# BLT_Preliminary_Avionics_Schematic_Brand.net
KiCad netlist of a schematic drawn in EAGLE
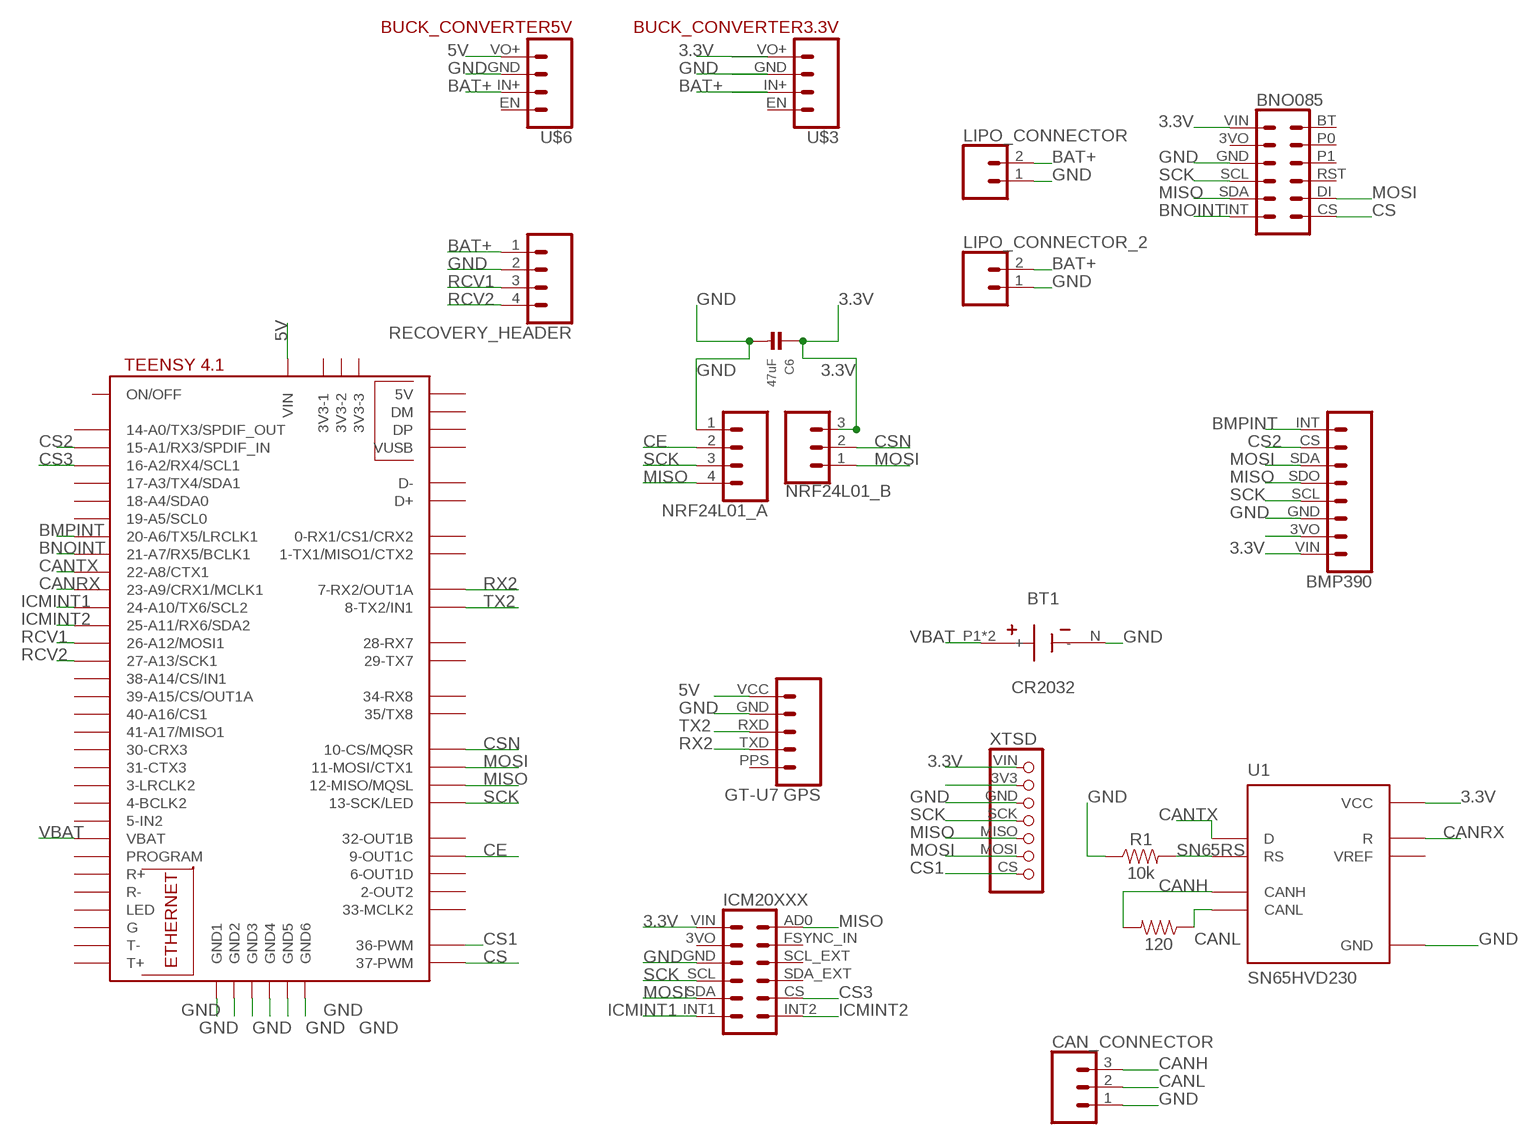
[diagram p0: schematic, sheet 1]

(export (version "E")
  (design (tool "Eeschema 10.0.6"))
  (components
    (comp (ref "120")
      (value "RESISTOR1206")
      (footprint "eagle-import:1206")
      (libsource (lib "eagle-import") (part "RESISTOR1206"))
    )
    (comp (ref "BT1")
      (value "CR2032")
      (footprint "eagle-import:BAT_3003")
      (fields (field (name "MANUFACTURER") "Keystone Electronics") (field (name "MPN") "3003"))
      (libsource (lib "eagle-import") (part "COIN-CELL-THM-3P?--3003CR2032"))
    )
    (comp (ref "C6")
      (value "47uF")
      (footprint "eagle-import:0805")
      (libsource (lib "eagle-import") (part "CAP_CERAMIC0805"))
    )
    (comp (ref "CAN_CONNECTOR")
      (value "CONN_03")
      (footprint "eagle-import:1X03")
      (libsource (lib "eagle-import") (part "CONN_03"))
    )
    (comp (ref "LIPO_CONNECTOR")
      (value "CONN_02PTH4")
      (footprint "eagle-import:1X02_XTRA_BIG")
      (libsource (lib "eagle-import") (part "CONN_02PTH4"))
    )
    (comp (ref "LIPO_CONNECTOR_2")
      (value "CONN_02")
      (footprint "eagle-import:1X02")
      (libsource (lib "eagle-import") (part "CONN_02"))
    )
    (comp (ref "NRF24L01_A")
      (value "CONN_04")
      (footprint "eagle-import:1X04")
      (libsource (lib "eagle-import") (part "CONN_04"))
    )
    (comp (ref "NRF24L01_B")
      (value "CONN_03")
      (footprint "eagle-import:1X03")
      (libsource (lib "eagle-import") (part "CONN_03"))
    )
    (comp (ref "R1")
      (value "10k")
      (footprint "eagle-import:0603")
      (libsource (lib "eagle-import") (part "10KOHM-0603-1/10W-1%"))
    )
    (comp (ref "RECOVERY_HEADER")
      (value "CONN_04")
      (footprint "eagle-import:1X04")
      (libsource (lib "eagle-import") (part "CONN_04"))
    )
    (comp (ref "U$1")
      (value "TEENSY41")
      (footprint "eagle-import:TEENSY41")
      (libsource (lib "eagle-import") (part "TEENSY41"))
    )
    (comp (ref "U$2")
      (value "BMP390")
      (footprint "eagle-import:MICROBUILDER_1X08_ROUND")
      (libsource (lib "eagle-import") (part "BMP390"))
    )
    (comp (ref "U$3")
      (value "BUCK_CONVERTER3.3V")
      (footprint "eagle-import:1X04")
      (fields (field (name "VOLTAGE") "3.3V"))
      (libsource (lib "eagle-import") (part "BUCK_CONVERTER3.3V"))
    )
    (comp (ref "U$4")
      (value "GT-U7_GPS")
      (footprint "eagle-import:1X05")
      (libsource (lib "eagle-import") (part "GT-U7_GPS"))
    )
    (comp (ref "U$5")
      (value "XTSDXTSD_PINS")
      (footprint "eagle-import:1X07")
      (libsource (lib "eagle-import") (part "XTSDXTSD_PINS"))
    )
    (comp (ref "U$6")
      (value "BUCK_CONVERTER5V")
      (footprint "eagle-import:1X04")
      (fields (field (name "VOLTAGE") "5V"))
      (libsource (lib "eagle-import") (part "BUCK_CONVERTER5V"))
    )
    (comp (ref "U$7")
      (value "BNO085")
      (footprint "eagle-import:MICROBUILDER_1X06_ROUND_70")
      (libsource (lib "eagle-import") (part "BNO085"))
    )
    (comp (ref "U$8")
      (value "ICM20XXX")
      (footprint "eagle-import:1X06")
      (libsource (lib "eagle-import") (part "ICM20XXX"))
    )
    (comp (ref "U1")
      (value "SN65HVD230")
      (footprint "eagle-import:SOIC127P599X175-8N")
      (fields (field (name "MF") "Texas Instruments"))
      (libsource (lib "eagle-import") (part "SN65HVD230"))
    )
  )
  (nets
    (net (code "1") (name "/3.3V") (class "Default")
      (node (ref "C6") (pin "1") (pinfunction "P$1_1") (pintype "passive"))
      (node (ref "NRF24L01_B") (pin "3") (pinfunction "3_3") (pintype "passive"))
      (node (ref "U$2") (pin "VIN") (pinfunction "VIN_VIN") (pintype "passive"))
      (node (ref "U$3") (pin "VO+") (pinfunction "VO+_VO+") (pintype "passive"))
      (node (ref "U$5") (pin "VIN") (pinfunction "VIN_VIN") (pintype "passive"))
      (node (ref "U$7") (pin "VIN") (pinfunction "VIN_VIN") (pintype "passive"))
      (node (ref "U$8") (pin "VIN") (pinfunction "VCC_VIN") (pintype "passive"))
      (node (ref "U1") (pin "3") (pinfunction "VCC_3") (pintype "power_in"))
    )
    (net (code "2") (name "/5V") (class "Default")
      (node (ref "U$1") (pin "VIN") (pinfunction "VIN_VIN") (pintype "bidirectional"))
      (node (ref "U$4") (pin "VCC") (pinfunction "VCC_VCC") (pintype "passive"))
      (node (ref "U$6") (pin "VO+") (pinfunction "VO+_VO+") (pintype "passive"))
    )
    (net (code "3") (name "/BAT+") (class "Default")
      (node (ref "LIPO_CONNECTOR") (pin "2") (pinfunction "2_2") (pintype "passive"))
      (node (ref "LIPO_CONNECTOR_2") (pin "2") (pinfunction "2_2") (pintype "passive"))
      (node (ref "RECOVERY_HEADER") (pin "1") (pinfunction "1_1") (pintype "passive"))
      (node (ref "U$3") (pin "IN+") (pinfunction "IN+_IN+") (pintype "passive"))
      (node (ref "U$6") (pin "IN+") (pinfunction "IN+_IN+") (pintype "passive"))
    )
    (net (code "4") (name "/BMPINT") (class "Default")
      (node (ref "U$1") (pin "20-A6/TX5/LRCLK1") (pinfunction "20-A6/TX5/LRCLK1_20-A6/TX5/LRCLK1") (pintype "bidirectional"))
      (node (ref "U$2") (pin "INT") (pinfunction "INT_INT") (pintype "passive"))
    )
    (net (code "5") (name "/BNOINT") (class "Default")
      (node (ref "U$1") (pin "21-A7/RX5/BCLK1") (pinfunction "21-A7/RX5/BCLK1_21-A7/RX5/BCLK1") (pintype "bidirectional"))
      (node (ref "U$7") (pin "INT") (pinfunction "INT_INT") (pintype "passive"))
    )
    (net (code "6") (name "/CANH") (class "Default")
      (node (ref "120") (pin "2") (pinfunction "2_2") (pintype "passive"))
      (node (ref "CAN_CONNECTOR") (pin "3") (pinfunction "3_3") (pintype "passive"))
      (node (ref "U1") (pin "7") (pinfunction "CANH_7") (pintype "bidirectional"))
    )
    (net (code "7") (name "/CANL") (class "Default")
      (node (ref "120") (pin "1") (pinfunction "1_1") (pintype "passive"))
      (node (ref "CAN_CONNECTOR") (pin "2") (pinfunction "2_2") (pintype "passive"))
      (node (ref "U1") (pin "6") (pinfunction "CANL_6") (pintype "bidirectional"))
    )
    (net (code "8") (name "/CANRX") (class "Default")
      (node (ref "U$1") (pin "23-A9/CRX1/MCLK1") (pinfunction "23-A9/CRX1/MCLK1_23-A9/CRX1/MCLK1") (pintype "bidirectional"))
      (node (ref "U1") (pin "4") (pinfunction "R_4") (pintype "output"))
    )
    (net (code "9") (name "/CANTX") (class "Default")
      (node (ref "U$1") (pin "22-A8/CTX1") (pinfunction "22-A8/CTX1_22-A8/CTX1") (pintype "bidirectional"))
      (node (ref "U1") (pin "1") (pinfunction "D_1") (pintype "input"))
    )
    (net (code "10") (name "/CE") (class "Default")
      (node (ref "NRF24L01_A") (pin "2") (pinfunction "2_2") (pintype "passive"))
      (node (ref "U$1") (pin "9-OUT1C") (pinfunction "9-OUT1C_9-OUT1C") (pintype "bidirectional"))
    )
    (net (code "11") (name "/CS") (class "Default")
      (node (ref "U$1") (pin "37-PWM") (pinfunction "37-PWM_37-PWM") (pintype "bidirectional"))
      (node (ref "U$7") (pin "CS") (pinfunction "CS_CS") (pintype "passive"))
    )
    (net (code "12") (name "/CS1") (class "Default")
      (node (ref "U$1") (pin "36-PWM") (pinfunction "36-PWM_36-PWM") (pintype "bidirectional"))
      (node (ref "U$5") (pin "CS") (pinfunction "CS_CS") (pintype "passive"))
    )
    (net (code "13") (name "/CS2") (class "Default")
      (node (ref "U$1") (pin "15-A1/RX3/SPDIF_IN") (pinfunction "15-A1/RX3/SPDIF_IN_15-A1/RX3/SPDIF_IN") (pintype "bidirectional"))
      (node (ref "U$2") (pin "CS") (pinfunction "CS_CS") (pintype "passive"))
    )
    (net (code "14") (name "/CS3") (class "Default")
      (node (ref "U$1") (pin "16-A2/RX4/SCL1") (pinfunction "16-A2/RX4/SCL1_16-A2/RX4/SCL1") (pintype "bidirectional"))
      (node (ref "U$8") (pin "CS") (pinfunction "CS_CS") (pintype "passive"))
    )
    (net (code "15") (name "/CSN") (class "Default")
      (node (ref "NRF24L01_B") (pin "2") (pinfunction "2_2") (pintype "passive"))
      (node (ref "U$1") (pin "10-CS\\MQSR") (pinfunction "10-CS/MQSR_10-CS\\MQSR") (pintype "bidirectional"))
    )
    (net (code "16") (name "/GND") (class "Default")
      (node (ref "BT1") (pin "N") (pinfunction "-_N") (pintype "bidirectional"))
      (node (ref "C6") (pin "2") (pinfunction "P$2_2") (pintype "passive"))
      (node (ref "CAN_CONNECTOR") (pin "1") (pinfunction "1_1") (pintype "passive"))
      (node (ref "LIPO_CONNECTOR") (pin "1") (pinfunction "1_1") (pintype "passive"))
      (node (ref "LIPO_CONNECTOR_2") (pin "1") (pinfunction "1_1") (pintype "passive"))
      (node (ref "NRF24L01_A") (pin "1") (pinfunction "1_1") (pintype "passive"))
      (node (ref "R1") (pin "1") (pinfunction "1_1") (pintype "passive"))
      (node (ref "RECOVERY_HEADER") (pin "2") (pinfunction "2_2") (pintype "passive"))
      (node (ref "U$1") (pin "GND1") (pinfunction "GND1_GND1") (pintype "bidirectional"))
      (node (ref "U$1") (pin "GND2") (pinfunction "GND2_GND2") (pintype "bidirectional"))
      (node (ref "U$1") (pin "GND3") (pinfunction "GND3_GND3") (pintype "bidirectional"))
      (node (ref "U$1") (pin "GND4") (pinfunction "GND4_GND4") (pintype "bidirectional"))
      (node (ref "U$1") (pin "GND5") (pinfunction "GND5_GND5") (pintype "bidirectional"))
      (node (ref "U$1") (pin "GND6") (pinfunction "GND6_GND6") (pintype "bidirectional"))
      (node (ref "U$2") (pin "GND") (pinfunction "GND_GND") (pintype "passive"))
      (node (ref "U$3") (pin "GND") (pinfunction "GND_GND") (pintype "passive"))
      (node (ref "U$4") (pin "GND") (pinfunction "GND_GND") (pintype "passive"))
      (node (ref "U$5") (pin "GND") (pinfunction "GND_GND") (pintype "passive"))
      (node (ref "U$6") (pin "GND") (pinfunction "GND_GND") (pintype "passive"))
      (node (ref "U$7") (pin "GND") (pinfunction "GND_GND") (pintype "passive"))
      (node (ref "U$8") (pin "GND") (pinfunction "GND_GND") (pintype "passive"))
      (node (ref "U1") (pin "2") (pinfunction "GND_2") (pintype "power_in"))
    )
    (net (code "17") (name "/ICMINT1") (class "Default")
      (node (ref "U$1") (pin "24-A10/TX6/SCL2") (pinfunction "24-A10/TX6/SCL2_24-A10/TX6/SCL2") (pintype "bidirectional"))
      (node (ref "U$8") (pin "INT1") (pinfunction "INT1_INT1") (pintype "passive"))
    )
    (net (code "18") (name "/ICMINT2") (class "Default")
      (node (ref "U$1") (pin "25-A11/RX6/SDA2") (pinfunction "25-A11/RX6/SDA2_25-A11/RX6/SDA2") (pintype "bidirectional"))
      (node (ref "U$8") (pin "INT2") (pinfunction "INT2_INT2") (pintype "passive"))
    )
    (net (code "19") (name "/MISO") (class "Default")
      (node (ref "NRF24L01_A") (pin "4") (pinfunction "4_4") (pintype "passive"))
      (node (ref "U$1") (pin "12-MISO/MQSL") (pinfunction "12-MISO/MQSL_12-MISO/MQSL") (pintype "bidirectional"))
      (node (ref "U$2") (pin "SDO") (pinfunction "SDO_SDO") (pintype "passive"))
      (node (ref "U$5") (pin "MISO") (pinfunction "MISO_MISO") (pintype "passive"))
      (node (ref "U$7") (pin "SDA") (pinfunction "SDA_SDA") (pintype "passive"))
      (node (ref "U$8") (pin "AD0") (pinfunction "AD0_AD0") (pintype "passive"))
    )
    (net (code "20") (name "/MOSI") (class "Default")
      (node (ref "NRF24L01_B") (pin "1") (pinfunction "1_1") (pintype "passive"))
      (node (ref "U$1") (pin "11-MOSI/CTX1") (pinfunction "11-MOSI/CTX1_11-MOSI/CTX1") (pintype "bidirectional"))
      (node (ref "U$2") (pin "SDA") (pinfunction "SDA_SDA") (pintype "passive"))
      (node (ref "U$5") (pin "MOSI") (pinfunction "MOSI_MOSI") (pintype "passive"))
      (node (ref "U$7") (pin "DI") (pinfunction "DI_DI") (pintype "passive"))
      (node (ref "U$8") (pin "SDA") (pinfunction "SDA_SDA") (pintype "passive"))
    )
    (net (code "21") (name "/RCV1") (class "Default")
      (node (ref "RECOVERY_HEADER") (pin "3") (pinfunction "3_3") (pintype "passive"))
      (node (ref "U$1") (pin "26-A12/MOSI1") (pinfunction "26-A12/MOSI1_26-A12/MOSI1") (pintype "bidirectional"))
    )
    (net (code "22") (name "/RCV2") (class "Default")
      (node (ref "RECOVERY_HEADER") (pin "4") (pinfunction "4_4") (pintype "passive"))
      (node (ref "U$1") (pin "27-A13/SCK1") (pinfunction "27-A13/SCK1_27-A13/SCK1") (pintype "bidirectional"))
    )
    (net (code "23") (name "/RX2") (class "Default")
      (node (ref "U$1") (pin "7-RX2/OUT1A") (pinfunction "7-RX2/OUT1A_7-RX2/OUT1A") (pintype "bidirectional"))
      (node (ref "U$4") (pin "TXD") (pinfunction "TXD_TXD") (pintype "passive"))
    )
    (net (code "24") (name "/SCK") (class "Default")
      (node (ref "NRF24L01_A") (pin "3") (pinfunction "3_3") (pintype "passive"))
      (node (ref "U$1") (pin "13-SCK/LED") (pinfunction "13-SCK/LED_13-SCK/LED") (pintype "bidirectional"))
      (node (ref "U$2") (pin "SCL") (pinfunction "SCL_SCL") (pintype "passive"))
      (node (ref "U$5") (pin "SCK") (pinfunction "SCK_SCK") (pintype "passive"))
      (node (ref "U$7") (pin "SCL") (pinfunction "SCL_SCL") (pintype "passive"))
      (node (ref "U$8") (pin "SCL") (pinfunction "SCL_SCL") (pintype "passive"))
    )
    (net (code "25") (name "/SN65RS") (class "Default")
      (node (ref "R1") (pin "2") (pinfunction "2_2") (pintype "passive"))
      (node (ref "U1") (pin "8") (pinfunction "RS_8") (pintype "input"))
    )
    (net (code "26") (name "/TX2") (class "Default")
      (node (ref "U$1") (pin "8-TX2/IN1") (pinfunction "8-TX2/IN1_8-TX2/IN1") (pintype "bidirectional"))
      (node (ref "U$4") (pin "RXD") (pinfunction "RXD_RXD") (pintype "passive"))
    )
    (net (code "27") (name "/VBAT") (class "Default")
      (node (ref "BT1") (pin "P1") (pinfunction "+_P1") (pintype "bidirectional"))
      (node (ref "BT1") (pin "P2") (pinfunction "+_P2") (pintype "bidirectional"))
      (node (ref "U$1") (pin "VBAT") (pinfunction "VBAT_VBAT") (pintype "bidirectional"))
    )
    (net (code "28") (name "unconnected-(U$1-5V-Pad+5V)") (class "Default")
      (node (ref "U$1") (pin "+5V") (pinfunction "5V_+5V") (pintype "bidirectional"))
    )
    (net (code "29") (name "unconnected-(U$1-35{slash}TX8-Pad35-TX8)") (class "Default")
      (node (ref "U$1") (pin "35-TX8") (pinfunction "35/TX8_35-TX8") (pintype "bidirectional"))
    )
    (net (code "30") (name "unconnected-(U$1-Pad0-RX1{slash}CS1{slash}CRX2)") (class "Default")
      (node (ref "U$1") (pin "0-RX1/CS1/CRX2") (pinfunction "0-RX1/CS1/CRX2_0-RX1/CS1/CRX2") (pintype "bidirectional"))
    )
    (net (code "31") (name "unconnected-(U$1-Pad1-TX1{slash}MISO1{slash}CTX2)") (class "Default")
      (node (ref "U$1") (pin "1-TX1/MISO1/CTX2") (pinfunction "1-TX1/MISO1/CTX2_1-TX1/MISO1/CTX2") (pintype "bidirectional"))
    )
    (net (code "32") (name "unconnected-(U$1-Pad2-OUT2)") (class "Default")
      (node (ref "U$1") (pin "2-OUT2") (pinfunction "2-OUT2_2-OUT2") (pintype "bidirectional"))
    )
    (net (code "33") (name "unconnected-(U$1-Pad3-LRCLK2)") (class "Default")
      (node (ref "U$1") (pin "3-LRCLK2") (pinfunction "3-LRCLK2_3-LRCLK2") (pintype "bidirectional"))
    )
    (net (code "34") (name "unconnected-(U$1-Pad3V3-1)") (class "Default")
      (node (ref "U$1") (pin "3V3-1") (pinfunction "3V3-1_3V3-1") (pintype "bidirectional"))
    )
    (net (code "35") (name "unconnected-(U$1-Pad3V3-2)") (class "Default")
      (node (ref "U$1") (pin "3V3-2") (pinfunction "3V3-2_3V3-2") (pintype "bidirectional"))
    )
    (net (code "36") (name "unconnected-(U$1-Pad3V3-3)") (class "Default")
      (node (ref "U$1") (pin "3V3-3") (pinfunction "3V3-3_3V3-3") (pintype "bidirectional"))
    )
    (net (code "37") (name "unconnected-(U$1-Pad4-BCLK2)") (class "Default")
      (node (ref "U$1") (pin "4-BCLK2") (pinfunction "4-BCLK2_4-BCLK2") (pintype "bidirectional"))
    )
    (net (code "38") (name "unconnected-(U$1-Pad5-IN2)") (class "Default")
      (node (ref "U$1") (pin "5-IN2") (pinfunction "5-IN2_5-IN2") (pintype "bidirectional"))
    )
    (net (code "39") (name "unconnected-(U$1-Pad6-OUT1D)") (class "Default")
      (node (ref "U$1") (pin "6-OUT1D") (pinfunction "6-OUT1D_6-OUT1D") (pintype "bidirectional"))
    )
    (net (code "40") (name "unconnected-(U$1-Pad14-A0{slash}TX3{slash}SPDIF_OUT)") (class "Default")
      (node (ref "U$1") (pin "14-A0/TX3/SPDIF_OUT") (pinfunction "14-A0/TX3/SPDIF_OUT_14-A0/TX3/SPDIF_OUT") (pintype "bidirectional"))
    )
    (net (code "41") (name "unconnected-(U$1-Pad17-A3{slash}TX4{slash}SDA1)") (class "Default")
      (node (ref "U$1") (pin "17-A3/TX4/SDA1") (pinfunction "17-A3/TX4/SDA1_17-A3/TX4/SDA1") (pintype "bidirectional"))
    )
    (net (code "42") (name "unconnected-(U$1-Pad18-A4{slash}SDA0)") (class "Default")
      (node (ref "U$1") (pin "18-A4/SDA0") (pinfunction "18-A4/SDA0_18-A4/SDA0") (pintype "bidirectional"))
    )
    (net (code "43") (name "unconnected-(U$1-Pad19-A5{slash}SCL0)") (class "Default")
      (node (ref "U$1") (pin "19-A5/SCL0") (pinfunction "19-A5/SCL0_19-A5/SCL0") (pintype "bidirectional"))
    )
    (net (code "44") (name "unconnected-(U$1-Pad28-RX7)") (class "Default")
      (node (ref "U$1") (pin "28-RX7") (pinfunction "28-RX7_28-RX7") (pintype "bidirectional"))
    )
    (net (code "45") (name "unconnected-(U$1-Pad29-TX7)") (class "Default")
      (node (ref "U$1") (pin "29-TX7") (pinfunction "29-TX7_29-TX7") (pintype "bidirectional"))
    )
    (net (code "46") (name "unconnected-(U$1-Pad30-CRX3)") (class "Default")
      (node (ref "U$1") (pin "30-CRX3") (pinfunction "30-CRX3_30-CRX3") (pintype "bidirectional"))
    )
    (net (code "47") (name "unconnected-(U$1-Pad31-CTX3)") (class "Default")
      (node (ref "U$1") (pin "31-CTX3") (pinfunction "31-CTX3_31-CTX3") (pintype "bidirectional"))
    )
    (net (code "48") (name "unconnected-(U$1-Pad32-OUT1B)") (class "Default")
      (node (ref "U$1") (pin "32-OUT1B") (pinfunction "32-OUT1B_32-OUT1B") (pintype "bidirectional"))
    )
    (net (code "49") (name "unconnected-(U$1-Pad33-MCLK2)") (class "Default")
      (node (ref "U$1") (pin "33-MCLK2") (pinfunction "33-MCLK2_33-MCLK2") (pintype "bidirectional"))
    )
    (net (code "50") (name "unconnected-(U$1-Pad34-RX8)") (class "Default")
      (node (ref "U$1") (pin "34-RX8") (pinfunction "34-RX8_34-RX8") (pintype "bidirectional"))
    )
    (net (code "51") (name "unconnected-(U$1-Pad38-A14{slash}CS{slash}IN1)") (class "Default")
      (node (ref "U$1") (pin "38-A14/CS/IN1") (pinfunction "38-A14/CS/IN1_38-A14/CS/IN1") (pintype "bidirectional"))
    )
    (net (code "52") (name "unconnected-(U$1-Pad39-A15{slash}CS{slash}OUT1A)") (class "Default")
      (node (ref "U$1") (pin "39-A15/CS/OUT1A") (pinfunction "39-A15/CS/OUT1A_39-A15/CS/OUT1A") (pintype "bidirectional"))
    )
    (net (code "53") (name "unconnected-(U$1-Pad40-A16{slash}CS1)") (class "Default")
      (node (ref "U$1") (pin "40-A16/CS1") (pinfunction "40-A16/CS1_40-A16/CS1") (pintype "bidirectional"))
    )
    (net (code "54") (name "unconnected-(U$1-Pad41-A17{slash}MISO1)") (class "Default")
      (node (ref "U$1") (pin "41-A17/MISO1") (pinfunction "41-A17/MISO1_41-A17/MISO1") (pintype "bidirectional"))
    )
    (net (code "55") (name "unconnected-(U$1-PadD+)") (class "Default")
      (node (ref "U$1") (pin "D+") (pinfunction "D+_D+") (pintype "bidirectional"))
    )
    (net (code "56") (name "unconnected-(U$1-PadD-)") (class "Default")
      (node (ref "U$1") (pin "D-") (pinfunction "D-_D-") (pintype "bidirectional"))
    )
    (net (code "57") (name "unconnected-(U$1-PadDM)") (class "Default")
      (node (ref "U$1") (pin "DM") (pinfunction "DM_DM") (pintype "bidirectional"))
    )
    (net (code "58") (name "unconnected-(U$1-PadDP)") (class "Default")
      (node (ref "U$1") (pin "DP") (pinfunction "DP_DP") (pintype "bidirectional"))
    )
    (net (code "59") (name "unconnected-(U$1-PadG)") (class "Default")
      (node (ref "U$1") (pin "G") (pinfunction "G_G") (pintype "bidirectional"))
    )
    (net (code "60") (name "unconnected-(U$1-PadLED)") (class "Default")
      (node (ref "U$1") (pin "LED") (pinfunction "LED_LED") (pintype "bidirectional"))
    )
    (net (code "61") (name "unconnected-(U$1-PadON{slash}OFF)") (class "Default")
      (node (ref "U$1") (pin "ON/OFF") (pinfunction "ON/OFF_ON/OFF") (pintype "bidirectional"))
    )
    (net (code "62") (name "unconnected-(U$1-PadPROGRAM)") (class "Default")
      (node (ref "U$1") (pin "PROGRAM") (pinfunction "PROGRAM_PROGRAM") (pintype "bidirectional"))
    )
    (net (code "63") (name "unconnected-(U$1-PadR+)") (class "Default")
      (node (ref "U$1") (pin "R+") (pinfunction "R+_R+") (pintype "bidirectional"))
    )
    (net (code "64") (name "unconnected-(U$1-PadR-)") (class "Default")
      (node (ref "U$1") (pin "R-") (pinfunction "R-_R-") (pintype "bidirectional"))
    )
    (net (code "65") (name "unconnected-(U$1-PadT+)") (class "Default")
      (node (ref "U$1") (pin "T+") (pinfunction "T+_T+") (pintype "bidirectional"))
    )
    (net (code "66") (name "unconnected-(U$1-PadT-)") (class "Default")
      (node (ref "U$1") (pin "T-") (pinfunction "T-_T-") (pintype "bidirectional"))
    )
    (net (code "67") (name "unconnected-(U$1-PadVUSB)") (class "Default")
      (node (ref "U$1") (pin "VUSB") (pinfunction "VUSB_VUSB") (pintype "bidirectional"))
    )
    (net (code "68") (name "unconnected-(U$2-Pad3VO)") (class "Default")
      (node (ref "U$2") (pin "3VO") (pinfunction "3VO_3VO") (pintype "passive"))
    )
    (net (code "69") (name "unconnected-(U$3-PadEN)") (class "Default")
      (node (ref "U$3") (pin "EN") (pinfunction "EN_EN") (pintype "passive"))
    )
    (net (code "70") (name "unconnected-(U$4-PadPPS)") (class "Default")
      (node (ref "U$4") (pin "PPS") (pinfunction "PPS_PPS") (pintype "passive"))
    )
    (net (code "71") (name "unconnected-(U$5-Pad3V3)") (class "Default")
      (node (ref "U$5") (pin "3V3") (pinfunction "3V3_3V3") (pintype "passive"))
    )
    (net (code "72") (name "unconnected-(U$6-PadEN)") (class "Default")
      (node (ref "U$6") (pin "EN") (pinfunction "EN_EN") (pintype "passive"))
    )
    (net (code "73") (name "unconnected-(U$7-Pad3VO)") (class "Default")
      (node (ref "U$7") (pin "3VO") (pinfunction "3VO_3VO") (pintype "passive"))
    )
    (net (code "74") (name "unconnected-(U$7-PadBT)") (class "Default")
      (node (ref "U$7") (pin "BT") (pinfunction "BT_BT") (pintype "passive"))
    )
    (net (code "75") (name "unconnected-(U$7-PadP0)") (class "Default")
      (node (ref "U$7") (pin "P0") (pinfunction "P0_P0") (pintype "passive"))
    )
    (net (code "76") (name "unconnected-(U$7-PadP1)") (class "Default")
      (node (ref "U$7") (pin "P1") (pinfunction "P1_P1") (pintype "passive"))
    )
    (net (code "77") (name "unconnected-(U$7-PadRST)") (class "Default")
      (node (ref "U$7") (pin "RST") (pinfunction "RST_RST") (pintype "passive"))
    )
    (net (code "78") (name "unconnected-(U$8-Pad3VO)") (class "Default")
      (node (ref "U$8") (pin "3VO") (pinfunction "3VO_3VO") (pintype "passive"))
    )
    (net (code "79") (name "unconnected-(U$8-PadFSYNC_IN)") (class "Default")
      (node (ref "U$8") (pin "FSYNC_IN") (pinfunction "FSYNC_IN_FSYNC_IN") (pintype "passive"))
    )
    (net (code "80") (name "unconnected-(U$8-PadSCL_EXT)") (class "Default")
      (node (ref "U$8") (pin "SCL_EXT") (pinfunction "SCL_EXT_SCL_EXT") (pintype "passive"))
    )
    (net (code "81") (name "unconnected-(U$8-PadSDA_EXT)") (class "Default")
      (node (ref "U$8") (pin "SDA_EXT") (pinfunction "SDA_EXT_SDA_EXT") (pintype "passive"))
    )
    (net (code "82") (name "unconnected-(U1-VREF-Pad5)") (class "Default")
      (node (ref "U1") (pin "5") (pinfunction "VREF_5") (pintype "output"))
    )
  )
)
